# stepper-motor-driver.net
KiCad netlist of a schematic drawn in EAGLE
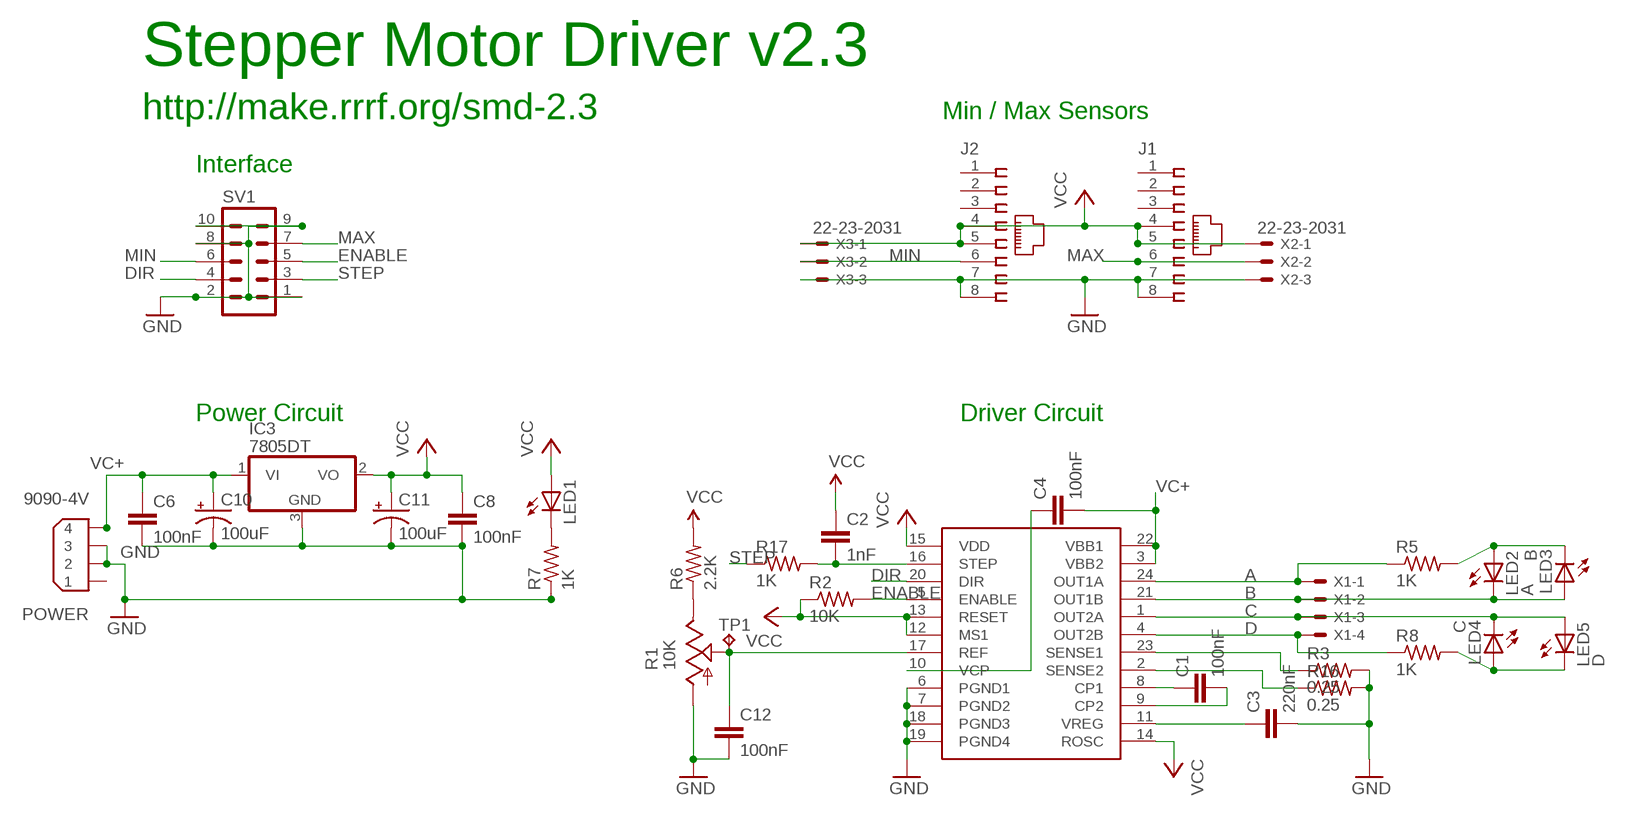
[diagram p0: schematic, sheet 1]

(export (version "E")
  (design (tool "Eeschema 10.0.6"))
  (components
    (comp (ref "C1")
      (value "100nF")
      (footprint "eagle-import:C1206")
      (libsource (lib "eagle-import") (part "C-EUC1206"))
    )
    (comp (ref "C2")
      (value "1nF")
      (footprint "eagle-import:C1206K")
      (libsource (lib "eagle-import") (part "C-EUC1206K"))
    )
    (comp (ref "C3")
      (value "220nF")
      (footprint "eagle-import:C1206")
      (libsource (lib "eagle-import") (part "C-EUC1206"))
    )
    (comp (ref "C4")
      (value "100nF")
      (footprint "eagle-import:C1206")
      (libsource (lib "eagle-import") (part "C-EUC1206"))
    )
    (comp (ref "C6")
      (value "100nF")
      (footprint "eagle-import:C1206K")
      (libsource (lib "eagle-import") (part "C-EUC1206K"))
    )
    (comp (ref "C8")
      (value "100nF")
      (footprint "eagle-import:C1206K")
      (libsource (lib "eagle-import") (part "C-EUC1206K"))
    )
    (comp (ref "C10")
      (value "100uF")
      (footprint "eagle-import:UD-10X10_NICHICON")
      (libsource (lib "eagle-import") (part "CPOL-USUD-10X10"))
    )
    (comp (ref "C11")
      (value "100uF")
      (footprint "eagle-import:UD-10X10_NICHICON")
      (libsource (lib "eagle-import") (part "CPOL-USUD-10X10"))
    )
    (comp (ref "C12")
      (value "100nF")
      (footprint "eagle-import:C1206")
      (libsource (lib "eagle-import") (part "resistor_C-EUC1206"))
    )
    (comp (ref "DRIVER")
      (value "A3982")
      (footprint "eagle-import:SO24W")
      (libsource (lib "eagle-import") (part "A3982SOIC24"))
    )
    (comp (ref "IC3")
      (value "7805DT")
      (footprint "eagle-import:TO252")
      (libsource (lib "eagle-import") (part "78DT05"))
    )
    (comp (ref "J1")
      (value "520426-4")
      (footprint "eagle-import:520426-4")
      (libsource (lib "eagle-import") (part "520426-4"))
    )
    (comp (ref "J2")
      (value "520426-4")
      (footprint "eagle-import:520426-4")
      (libsource (lib "eagle-import") (part "520426-4"))
    )
    (comp (ref "LED1")
      (value "LEDCHIPLED_1206")
      (footprint "eagle-import:CHIPLED_1206")
      (libsource (lib "eagle-import") (part "LEDCHIPLED_1206"))
    )
    (comp (ref "LED2")
      (value "A")
      (footprint "eagle-import:CHIPLED_1206")
      (libsource (lib "eagle-import") (part "LEDCHIPLED_1206"))
    )
    (comp (ref "LED3")
      (value "B")
      (footprint "eagle-import:CHIPLED_1206")
      (libsource (lib "eagle-import") (part "LEDCHIPLED_1206"))
    )
    (comp (ref "LED4")
      (value "C")
      (footprint "eagle-import:CHIPLED_1206")
      (libsource (lib "eagle-import") (part "LEDCHIPLED_1206"))
    )
    (comp (ref "LED5")
      (value "D")
      (footprint "eagle-import:CHIPLED_1206")
      (libsource (lib "eagle-import") (part "LEDCHIPLED_1206"))
    )
    (comp (ref "POWER")
      (value "9090-4V")
      (footprint "eagle-import:9090-4V")
      (libsource (lib "eagle-import") (part "9090-4V"))
    )
    (comp (ref "R1")
      (value "10K")
      (footprint "eagle-import:B25P")
      (libsource (lib "eagle-import") (part "TRIM_US-B25P"))
    )
    (comp (ref "R2")
      (value "10K")
      (footprint "eagle-import:R1206")
      (libsource (lib "eagle-import") (part "resistor_R-US_R1206"))
    )
    (comp (ref "R3")
      (value "0.25")
      (footprint "eagle-import:R2512")
      (libsource (lib "eagle-import") (part "R-US_R2512"))
    )
    (comp (ref "R5")
      (value "1K")
      (footprint "eagle-import:R1206")
      (libsource (lib "eagle-import") (part "resistor_R-US_R1206"))
    )
    (comp (ref "R6")
      (value "2.2K")
      (footprint "eagle-import:R1206")
      (libsource (lib "eagle-import") (part "R-US_R1206"))
    )
    (comp (ref "R7")
      (value "1K")
      (footprint "eagle-import:R1206")
      (libsource (lib "eagle-import") (part "R-US_R1206"))
    )
    (comp (ref "R8")
      (value "1K")
      (footprint "eagle-import:R1206")
      (libsource (lib "eagle-import") (part "R-US_R1206"))
    )
    (comp (ref "R16")
      (value "0.25")
      (footprint "eagle-import:R2512")
      (libsource (lib "eagle-import") (part "R-US_R2512"))
    )
    (comp (ref "R17")
      (value "1K")
      (footprint "eagle-import:R1206")
      (libsource (lib "eagle-import") (part "R-US_R1206"))
    )
    (comp (ref "SV1")
      (value "ML10")
      (footprint "eagle-import:ML10")
      (libsource (lib "eagle-import") (part "ML10"))
    )
    (comp (ref "TP1")
      (value "TPPAD1-13")
      (footprint "eagle-import:P1-13")
      (libsource (lib "eagle-import") (part "TPPAD1-13"))
    )
    (comp (ref "X1")
      (value "KK-156-4")
      (footprint "eagle-import:KK-156-4")
      (libsource (lib "eagle-import") (part "KK-156-4"))
    )
    (comp (ref "X2")
      (value "22-23-2031")
      (footprint "eagle-import:22-23-2031")
      (libsource (lib "eagle-import") (part "22-23-2031"))
    )
    (comp (ref "X3")
      (value "22-23-2031")
      (footprint "eagle-import:22-23-2031")
      (libsource (lib "eagle-import") (part "22-23-2031"))
    )
  )
  (nets
    (net (code "1") (name "/A") (class "Default")
      (node (ref "DRIVER") (pin "24") (pinfunction "OUT1A_24") (pintype "bidirectional"))
      (node (ref "R5") (pin "1") (pinfunction "1_1") (pintype "passive"))
      (node (ref "X1") (pin "1") (pinfunction "S_1") (pintype "passive"))
    )
    (net (code "2") (name "/B") (class "Default")
      (node (ref "DRIVER") (pin "21") (pinfunction "OUT1B_21") (pintype "bidirectional"))
      (node (ref "LED2") (pin "C") (pinfunction "C_C") (pintype "passive"))
      (node (ref "LED3") (pin "A") (pinfunction "A_A") (pintype "passive"))
      (node (ref "X1") (pin "2") (pinfunction "S_2") (pintype "passive"))
    )
    (net (code "3") (name "/C") (class "Default")
      (node (ref "DRIVER") (pin "1") (pinfunction "OUT2A_1") (pintype "bidirectional"))
      (node (ref "LED4") (pin "C") (pinfunction "C_C") (pintype "passive"))
      (node (ref "LED5") (pin "A") (pinfunction "A_A") (pintype "passive"))
      (node (ref "X1") (pin "3") (pinfunction "S_3") (pintype "passive"))
    )
    (net (code "4") (name "/D") (class "Default")
      (node (ref "DRIVER") (pin "4") (pinfunction "OUT2B_4") (pintype "bidirectional"))
      (node (ref "R8") (pin "1") (pinfunction "1_1") (pintype "passive"))
      (node (ref "X1") (pin "4") (pinfunction "S_4") (pintype "passive"))
    )
    (net (code "5") (name "/DIR") (class "Default")
      (node (ref "DRIVER") (pin "20") (pinfunction "DIR_20") (pintype "bidirectional"))
      (node (ref "SV1") (pin "4") (pinfunction "4_4") (pintype "passive"))
    )
    (net (code "6") (name "/ENABLE") (class "Default")
      (node (ref "DRIVER") (pin "5") (pinfunction "ENABLE_5") (pintype "bidirectional"))
      (node (ref "R2") (pin "2") (pinfunction "2_2") (pintype "passive"))
      (node (ref "SV1") (pin "5") (pinfunction "5_5") (pintype "passive"))
    )
    (net (code "7") (name "/MAX") (class "Default")
      (node (ref "J1") (pin "6") (pinfunction "6_6") (pintype "passive"))
      (node (ref "SV1") (pin "7") (pinfunction "7_7") (pintype "passive"))
      (node (ref "X2") (pin "2") (pinfunction "S_2") (pintype "passive"))
    )
    (net (code "8") (name "/MIN") (class "Default")
      (node (ref "J2") (pin "6") (pinfunction "6_6") (pintype "passive"))
      (node (ref "SV1") (pin "6") (pinfunction "6_6") (pintype "passive"))
      (node (ref "X3") (pin "2") (pinfunction "S_2") (pintype "passive"))
    )
    (net (code "9") (name "/STEP") (class "Default")
      (node (ref "R17") (pin "1") (pinfunction "1_1") (pintype "passive"))
      (node (ref "SV1") (pin "3") (pinfunction "3_3") (pintype "passive"))
    )
    (net (code "10") (name "/VC+") (class "Default")
      (node (ref "C10") (pin "+") (pinfunction "+_+") (pintype "passive"))
      (node (ref "C4") (pin "2") (pinfunction "2_2") (pintype "passive"))
      (node (ref "C6") (pin "1") (pinfunction "1_1") (pintype "passive"))
      (node (ref "DRIVER") (pin "22") (pinfunction "VBB1_22") (pintype "bidirectional"))
      (node (ref "DRIVER") (pin "3") (pinfunction "VBB2_3") (pintype "bidirectional"))
      (node (ref "IC3") (pin "1") (pinfunction "VI_1") (pintype "input"))
      (node (ref "POWER") (pin "4") (pinfunction "4_4") (pintype "passive"))
    )
    (net (code "11") (name "GND") (class "Default")
      (node (ref "C10") (pin "-") (pinfunction "-_-") (pintype "passive"))
      (node (ref "C11") (pin "-") (pinfunction "-_-") (pintype "passive"))
      (node (ref "C12") (pin "2") (pinfunction "2_2") (pintype "passive"))
      (node (ref "C3") (pin "2") (pinfunction "2_2") (pintype "passive"))
      (node (ref "C6") (pin "2") (pinfunction "2_2") (pintype "passive"))
      (node (ref "C8") (pin "2") (pinfunction "2_2") (pintype "passive"))
      (node (ref "DRIVER") (pin "18") (pinfunction "PGND3_18") (pintype "bidirectional"))
      (node (ref "DRIVER") (pin "19") (pinfunction "PGND4_19") (pintype "bidirectional"))
      (node (ref "DRIVER") (pin "6") (pinfunction "PGND1_6") (pintype "bidirectional"))
      (node (ref "DRIVER") (pin "7") (pinfunction "PGND2_7") (pintype "bidirectional"))
      (node (ref "IC3") (pin "3") (pinfunction "GND_3") (pintype "passive"))
      (node (ref "J1") (pin "7") (pinfunction "7_7") (pintype "passive"))
      (node (ref "J1") (pin "8") (pinfunction "8_8") (pintype "passive"))
      (node (ref "J2") (pin "7") (pinfunction "7_7") (pintype "passive"))
      (node (ref "J2") (pin "8") (pinfunction "8_8") (pintype "passive"))
      (node (ref "POWER") (pin "2") (pinfunction "2_2") (pintype "passive"))
      (node (ref "POWER") (pin "3") (pinfunction "3_3") (pintype "passive"))
      (node (ref "R1") (pin "A") (pinfunction "A_A") (pintype "passive"))
      (node (ref "R16") (pin "2") (pinfunction "2_2") (pintype "passive"))
      (node (ref "R3") (pin "2") (pinfunction "2_2") (pintype "passive"))
      (node (ref "R7") (pin "1") (pinfunction "1_1") (pintype "passive"))
      (node (ref "SV1") (pin "1") (pinfunction "1_1") (pintype "passive"))
      (node (ref "SV1") (pin "10") (pinfunction "10_10") (pintype "passive"))
      (node (ref "SV1") (pin "2") (pinfunction "2_2") (pintype "passive"))
      (node (ref "SV1") (pin "8") (pinfunction "8_8") (pintype "passive"))
      (node (ref "SV1") (pin "9") (pinfunction "9_9") (pintype "passive"))
      (node (ref "X2") (pin "3") (pinfunction "S_3") (pintype "passive"))
      (node (ref "X3") (pin "3") (pinfunction "S_3") (pintype "passive"))
    )
    (net (code "12") (name "Net-(DRIVER-CP1)") (class "Default")
      (node (ref "C1") (pin "1") (pinfunction "1_1") (pintype "passive"))
      (node (ref "DRIVER") (pin "8") (pinfunction "CP1_8") (pintype "bidirectional"))
    )
    (net (code "13") (name "Net-(DRIVER-CP2)") (class "Default")
      (node (ref "C1") (pin "2") (pinfunction "2_2") (pintype "passive"))
      (node (ref "DRIVER") (pin "9") (pinfunction "CP2_9") (pintype "bidirectional"))
    )
    (net (code "14") (name "Net-(DRIVER-REF)") (class "Default")
      (node (ref "C12") (pin "1") (pinfunction "1_1") (pintype "passive"))
      (node (ref "DRIVER") (pin "17") (pinfunction "REF_17") (pintype "bidirectional"))
      (node (ref "R1") (pin "S") (pinfunction "S_S") (pintype "passive"))
      (node (ref "TP1") (pin "1") (pinfunction "TP_1") (pintype "input"))
    )
    (net (code "15") (name "Net-(DRIVER-SENSE1)") (class "Default")
      (node (ref "DRIVER") (pin "23") (pinfunction "SENSE1_23") (pintype "bidirectional"))
      (node (ref "R3") (pin "1") (pinfunction "1_1") (pintype "passive"))
    )
    (net (code "16") (name "Net-(DRIVER-SENSE2)") (class "Default")
      (node (ref "DRIVER") (pin "2") (pinfunction "SENSE2_2") (pintype "bidirectional"))
      (node (ref "R16") (pin "1") (pinfunction "1_1") (pintype "passive"))
    )
    (net (code "17") (name "Net-(DRIVER-STEP)") (class "Default")
      (node (ref "C2") (pin "2") (pinfunction "2_2") (pintype "passive"))
      (node (ref "DRIVER") (pin "16") (pinfunction "STEP_16") (pintype "bidirectional"))
      (node (ref "R17") (pin "2") (pinfunction "2_2") (pintype "passive"))
    )
    (net (code "18") (name "Net-(DRIVER-VCP)") (class "Default")
      (node (ref "C4") (pin "1") (pinfunction "1_1") (pintype "passive"))
      (node (ref "DRIVER") (pin "10") (pinfunction "VCP_10") (pintype "bidirectional"))
    )
    (net (code "19") (name "Net-(DRIVER-VREG)") (class "Default")
      (node (ref "C3") (pin "1") (pinfunction "1_1") (pintype "passive"))
      (node (ref "DRIVER") (pin "11") (pinfunction "VREG_11") (pintype "bidirectional"))
    )
    (net (code "20") (name "Net-(LED1-PadC)") (class "Default")
      (node (ref "LED1") (pin "C") (pinfunction "C_C") (pintype "passive"))
      (node (ref "R7") (pin "2") (pinfunction "2_2") (pintype "passive"))
    )
    (net (code "21") (name "Net-(LED2-PadA)") (class "Default")
      (node (ref "LED2") (pin "A") (pinfunction "A_A") (pintype "passive"))
      (node (ref "LED3") (pin "C") (pinfunction "C_C") (pintype "passive"))
      (node (ref "R5") (pin "2") (pinfunction "2_2") (pintype "passive"))
    )
    (net (code "22") (name "Net-(LED4-PadA)") (class "Default")
      (node (ref "LED4") (pin "A") (pinfunction "A_A") (pintype "passive"))
      (node (ref "LED5") (pin "C") (pinfunction "C_C") (pintype "passive"))
      (node (ref "R8") (pin "2") (pinfunction "2_2") (pintype "passive"))
    )
    (net (code "23") (name "Net-(R1-PadE)") (class "Default")
      (node (ref "R1") (pin "E") (pinfunction "E_E") (pintype "passive"))
      (node (ref "R6") (pin "1") (pinfunction "1_1") (pintype "passive"))
    )
    (net (code "24") (name "VCC") (class "Default")
      (node (ref "C11") (pin "+") (pinfunction "+_+") (pintype "passive"))
      (node (ref "C2") (pin "1") (pinfunction "1_1") (pintype "passive"))
      (node (ref "C8") (pin "1") (pinfunction "1_1") (pintype "passive"))
      (node (ref "DRIVER") (pin "12") (pinfunction "MS1_12") (pintype "bidirectional"))
      (node (ref "DRIVER") (pin "13") (pinfunction "RESET_13") (pintype "bidirectional"))
      (node (ref "DRIVER") (pin "14") (pinfunction "ROSC_14") (pintype "bidirectional"))
      (node (ref "DRIVER") (pin "15") (pinfunction "VDD_15") (pintype "bidirectional"))
      (node (ref "IC3") (pin "2") (pinfunction "VO_2") (pintype "passive"))
      (node (ref "J1") (pin "4") (pinfunction "4_4") (pintype "passive"))
      (node (ref "J1") (pin "5") (pinfunction "5_5") (pintype "passive"))
      (node (ref "J2") (pin "4") (pinfunction "4_4") (pintype "passive"))
      (node (ref "J2") (pin "5") (pinfunction "5_5") (pintype "passive"))
      (node (ref "LED1") (pin "A") (pinfunction "A_A") (pintype "passive"))
      (node (ref "R2") (pin "1") (pinfunction "1_1") (pintype "passive"))
      (node (ref "R6") (pin "2") (pinfunction "2_2") (pintype "passive"))
      (node (ref "X2") (pin "1") (pinfunction "S_1") (pintype "passive"))
      (node (ref "X3") (pin "1") (pinfunction "S_1") (pintype "passive"))
    )
    (net (code "25") (name "unconnected-(J1-Pad1)") (class "Default")
      (node (ref "J1") (pin "1") (pinfunction "1_1") (pintype "passive"))
    )
    (net (code "26") (name "unconnected-(J1-Pad2)") (class "Default")
      (node (ref "J1") (pin "2") (pinfunction "2_2") (pintype "passive"))
    )
    (net (code "27") (name "unconnected-(J1-Pad3)") (class "Default")
      (node (ref "J1") (pin "3") (pinfunction "3_3") (pintype "passive"))
    )
    (net (code "28") (name "unconnected-(J2-Pad1)") (class "Default")
      (node (ref "J2") (pin "1") (pinfunction "1_1") (pintype "passive"))
    )
    (net (code "29") (name "unconnected-(J2-Pad2)") (class "Default")
      (node (ref "J2") (pin "2") (pinfunction "2_2") (pintype "passive"))
    )
    (net (code "30") (name "unconnected-(J2-Pad3)") (class "Default")
      (node (ref "J2") (pin "3") (pinfunction "3_3") (pintype "passive"))
    )
    (net (code "31") (name "unconnected-(POWER-Pad1)") (class "Default")
      (node (ref "POWER") (pin "1") (pinfunction "1_1") (pintype "passive"))
    )
  )
)
